# PAGE1.net
KiCad netlist of a schematic drawn in EAGLE
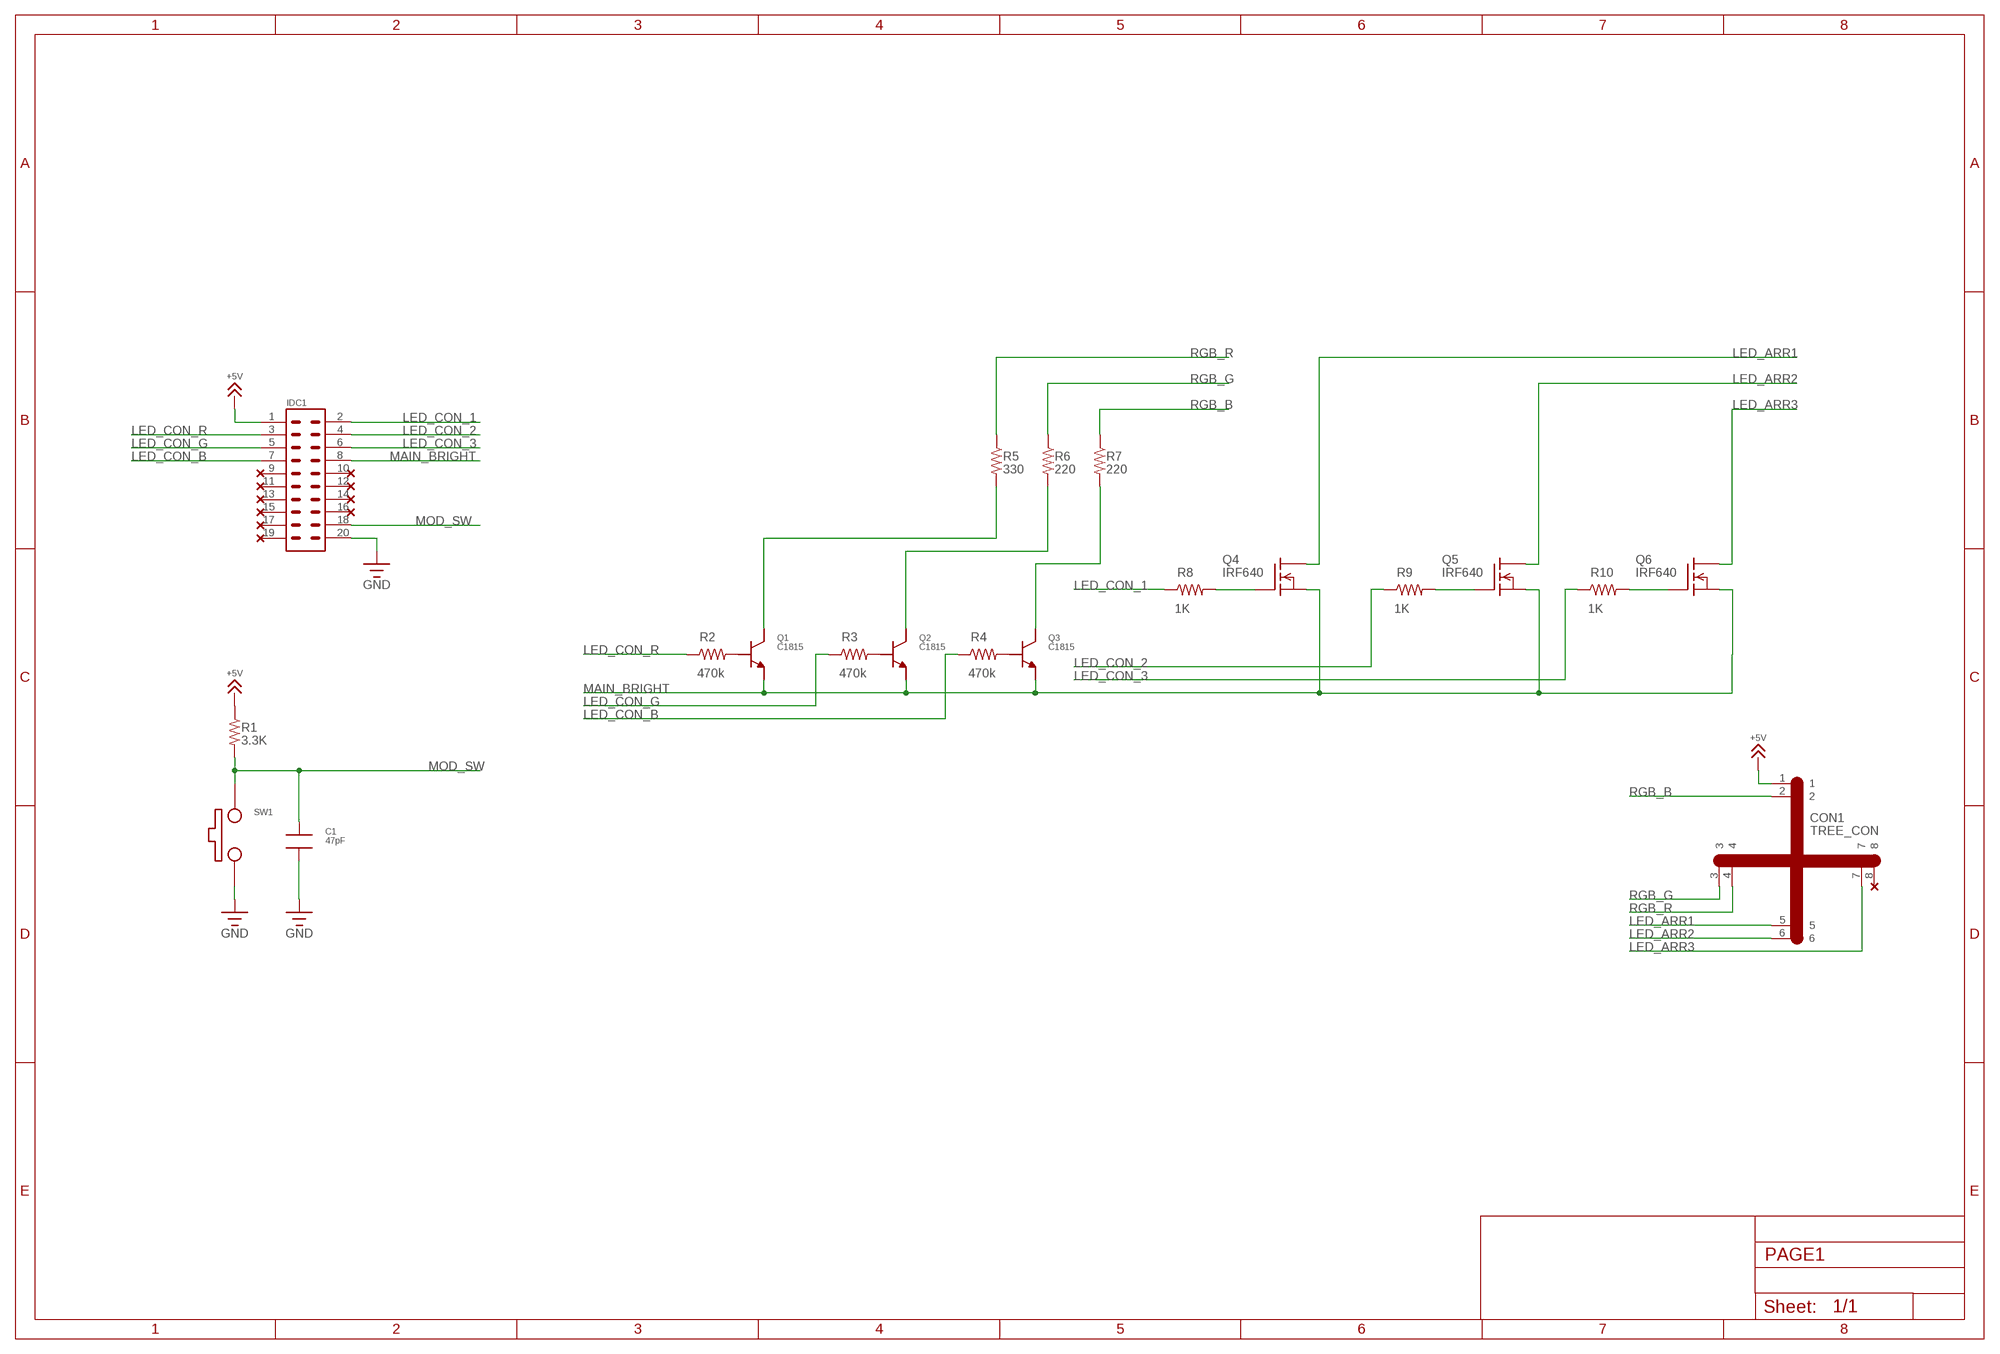
[diagram p0: schematic, sheet 1]

(export (version "E")
  (design (tool "Eeschema 10.0.6"))
  (components
    (comp (ref "C1")
      (value "47pF")
      (footprint "eagle-import:SMD2012")
      (libsource (lib "eagle-import") (part "CAP_NP_SMD2012"))
    )
    (comp (ref "CON1")
      (value "TREE_CON")
      (footprint "eagle-import:TREE_CON")
      (libsource (lib "eagle-import") (part "TREE_CON"))
    )
    (comp (ref "IDC1")
      (value "IDC20_BEN")
      (footprint "eagle-import:IDC20_BENDING")
      (libsource (lib "eagle-import") (part "IDC20_BEN"))
    )
    (comp (ref "Q1")
      (value "C1815")
      (footprint "eagle-import:TO92")
      (libsource (lib "eagle-import") (part "NPN"))
    )
    (comp (ref "Q2")
      (value "C1815")
      (footprint "eagle-import:TO92")
      (libsource (lib "eagle-import") (part "NPN"))
    )
    (comp (ref "Q3")
      (value "C1815")
      (footprint "eagle-import:TO92")
      (libsource (lib "eagle-import") (part "NPN"))
    )
    (comp (ref "Q4")
      (value "IRF640")
      (footprint "eagle-import:TO220")
      (libsource (lib "eagle-import") (part "IRF620"))
    )
    (comp (ref "Q5")
      (value "IRF640")
      (footprint "eagle-import:TO220")
      (libsource (lib "eagle-import") (part "IRF620"))
    )
    (comp (ref "Q6")
      (value "IRF640")
      (footprint "eagle-import:TO220")
      (libsource (lib "eagle-import") (part "IRF620"))
    )
    (comp (ref "R1")
      (value "3.3K")
      (footprint "eagle-import:SMD2012")
      (libsource (lib "eagle-import") (part "RES_2012"))
    )
    (comp (ref "R2")
      (value "470k")
      (footprint "eagle-import:SMD2012")
      (libsource (lib "eagle-import") (part "RES_2012"))
    )
    (comp (ref "R3")
      (value "470k")
      (footprint "eagle-import:SMD2012")
      (libsource (lib "eagle-import") (part "RES_2012"))
    )
    (comp (ref "R4")
      (value "470k")
      (footprint "eagle-import:SMD2012")
      (libsource (lib "eagle-import") (part "RES_2012"))
    )
    (comp (ref "R5")
      (value "330")
      (footprint "eagle-import:SMD2012")
      (libsource (lib "eagle-import") (part "RES_2012"))
    )
    (comp (ref "R6")
      (value "220")
      (footprint "eagle-import:SMD2012")
      (libsource (lib "eagle-import") (part "RES_2012"))
    )
    (comp (ref "R7")
      (value "220")
      (footprint "eagle-import:SMD2012")
      (libsource (lib "eagle-import") (part "RES_2012"))
    )
    (comp (ref "R8")
      (value "1K")
      (footprint "eagle-import:SMD2012")
      (libsource (lib "eagle-import") (part "RES_2012"))
    )
    (comp (ref "R9")
      (value "1K")
      (footprint "eagle-import:SMD2012")
      (libsource (lib "eagle-import") (part "RES_2012"))
    )
    (comp (ref "R10")
      (value "1K")
      (footprint "eagle-import:SMD2012")
      (libsource (lib "eagle-import") (part "RES_2012"))
    )
    (comp (ref "SW1")
      (value "PUSH_SW")
      (footprint "eagle-import:PUSH_SW")
      (libsource (lib "eagle-import") (part "PUSH_SW"))
    )
  )
  (nets
    (net (code "1") (name "+5V") (class "Default")
      (node (ref "CON1") (pin "1") (pinfunction "1_1") (pintype "passive"))
      (node (ref "IDC1") (pin "1") (pinfunction "1_1") (pintype "passive"))
      (node (ref "R1") (pin "1") (pinfunction "1_1") (pintype "passive"))
    )
    (net (code "2") (name "/LED_ARR1") (class "Default")
      (node (ref "CON1") (pin "5") (pinfunction "5_5") (pintype "passive"))
      (node (ref "Q4") (pin "2") (pinfunction "D_2") (pintype "passive"))
    )
    (net (code "3") (name "/LED_ARR2") (class "Default")
      (node (ref "CON1") (pin "6") (pinfunction "6_6") (pintype "passive"))
      (node (ref "Q5") (pin "2") (pinfunction "D_2") (pintype "passive"))
    )
    (net (code "4") (name "/LED_ARR3") (class "Default")
      (node (ref "CON1") (pin "7") (pinfunction "7_7") (pintype "passive"))
      (node (ref "Q6") (pin "2") (pinfunction "D_2") (pintype "passive"))
    )
    (net (code "5") (name "/LED_CON_1") (class "Default")
      (node (ref "IDC1") (pin "2") (pinfunction "2_2") (pintype "passive"))
      (node (ref "R8") (pin "1") (pinfunction "1_1") (pintype "passive"))
    )
    (net (code "6") (name "/LED_CON_2") (class "Default")
      (node (ref "IDC1") (pin "4") (pinfunction "4_4") (pintype "passive"))
      (node (ref "R9") (pin "1") (pinfunction "1_1") (pintype "passive"))
    )
    (net (code "7") (name "/LED_CON_3") (class "Default")
      (node (ref "IDC1") (pin "6") (pinfunction "6_6") (pintype "passive"))
      (node (ref "R10") (pin "1") (pinfunction "1_1") (pintype "passive"))
    )
    (net (code "8") (name "/LED_CON_B") (class "Default")
      (node (ref "IDC1") (pin "7") (pinfunction "7_7") (pintype "passive"))
      (node (ref "R4") (pin "1") (pinfunction "1_1") (pintype "passive"))
    )
    (net (code "9") (name "/LED_CON_G") (class "Default")
      (node (ref "IDC1") (pin "5") (pinfunction "5_5") (pintype "passive"))
      (node (ref "R3") (pin "1") (pinfunction "1_1") (pintype "passive"))
    )
    (net (code "10") (name "/LED_CON_R") (class "Default")
      (node (ref "IDC1") (pin "3") (pinfunction "3_3") (pintype "passive"))
      (node (ref "R2") (pin "1") (pinfunction "1_1") (pintype "passive"))
    )
    (net (code "11") (name "/MAIN_BRIGHT") (class "Default")
      (node (ref "IDC1") (pin "8") (pinfunction "8_8") (pintype "passive"))
      (node (ref "Q1") (pin "1") (pinfunction "E_1") (pintype "passive"))
      (node (ref "Q2") (pin "1") (pinfunction "E_1") (pintype "passive"))
      (node (ref "Q3") (pin "1") (pinfunction "E_1") (pintype "passive"))
      (node (ref "Q4") (pin "3") (pinfunction "S_3") (pintype "passive"))
      (node (ref "Q5") (pin "3") (pinfunction "S_3") (pintype "passive"))
      (node (ref "Q6") (pin "3") (pinfunction "S_3") (pintype "passive"))
    )
    (net (code "12") (name "/MOD_SW") (class "Default")
      (node (ref "C1") (pin "1") (pinfunction "1_1") (pintype "passive"))
      (node (ref "IDC1") (pin "18") (pinfunction "18_18") (pintype "passive"))
      (node (ref "R1") (pin "2") (pinfunction "2_2") (pintype "passive"))
      (node (ref "SW1") (pin "P$2") (pinfunction "P$2_P$2") (pintype "passive"))
    )
    (net (code "13") (name "/RGB_B") (class "Default")
      (node (ref "CON1") (pin "2") (pinfunction "2_2") (pintype "passive"))
      (node (ref "R7") (pin "1") (pinfunction "1_1") (pintype "passive"))
    )
    (net (code "14") (name "/RGB_G") (class "Default")
      (node (ref "CON1") (pin "3") (pinfunction "3_3") (pintype "passive"))
      (node (ref "R6") (pin "1") (pinfunction "1_1") (pintype "passive"))
    )
    (net (code "15") (name "/RGB_R") (class "Default")
      (node (ref "CON1") (pin "4") (pinfunction "4_4") (pintype "passive"))
      (node (ref "R5") (pin "1") (pinfunction "1_1") (pintype "passive"))
    )
    (net (code "16") (name "GND") (class "Default")
      (node (ref "C1") (pin "2") (pinfunction "2_2") (pintype "passive"))
      (node (ref "IDC1") (pin "20") (pinfunction "20_20") (pintype "passive"))
      (node (ref "SW1") (pin "P$1") (pinfunction "P$1_P$1") (pintype "passive"))
    )
    (net (code "17") (name "Net-(Q1-B)") (class "Default")
      (node (ref "Q1") (pin "3") (pinfunction "B_3") (pintype "passive"))
      (node (ref "R2") (pin "2") (pinfunction "2_2") (pintype "passive"))
    )
    (net (code "18") (name "Net-(Q1-C)") (class "Default")
      (node (ref "Q1") (pin "2") (pinfunction "C_2") (pintype "passive"))
      (node (ref "R5") (pin "2") (pinfunction "2_2") (pintype "passive"))
    )
    (net (code "19") (name "Net-(Q2-B)") (class "Default")
      (node (ref "Q2") (pin "3") (pinfunction "B_3") (pintype "passive"))
      (node (ref "R3") (pin "2") (pinfunction "2_2") (pintype "passive"))
    )
    (net (code "20") (name "Net-(Q2-C)") (class "Default")
      (node (ref "Q2") (pin "2") (pinfunction "C_2") (pintype "passive"))
      (node (ref "R6") (pin "2") (pinfunction "2_2") (pintype "passive"))
    )
    (net (code "21") (name "Net-(Q3-B)") (class "Default")
      (node (ref "Q3") (pin "3") (pinfunction "B_3") (pintype "passive"))
      (node (ref "R4") (pin "2") (pinfunction "2_2") (pintype "passive"))
    )
    (net (code "22") (name "Net-(Q3-C)") (class "Default")
      (node (ref "Q3") (pin "2") (pinfunction "C_2") (pintype "passive"))
      (node (ref "R7") (pin "2") (pinfunction "2_2") (pintype "passive"))
    )
    (net (code "23") (name "Net-(Q4-G)") (class "Default")
      (node (ref "Q4") (pin "1") (pinfunction "G_1") (pintype "passive"))
      (node (ref "R8") (pin "2") (pinfunction "2_2") (pintype "passive"))
    )
    (net (code "24") (name "Net-(Q5-G)") (class "Default")
      (node (ref "Q5") (pin "1") (pinfunction "G_1") (pintype "passive"))
      (node (ref "R9") (pin "2") (pinfunction "2_2") (pintype "passive"))
    )
    (net (code "25") (name "Net-(Q6-G)") (class "Default")
      (node (ref "Q6") (pin "1") (pinfunction "G_1") (pintype "passive"))
      (node (ref "R10") (pin "2") (pinfunction "2_2") (pintype "passive"))
    )
    (net (code "26") (name "unconnected-(CON1-Pad8)") (class "Default")
      (node (ref "CON1") (pin "8") (pinfunction "8_8") (pintype "passive"))
    )
    (net (code "27") (name "unconnected-(IDC1-Pad9)") (class "Default")
      (node (ref "IDC1") (pin "9") (pinfunction "9_9") (pintype "passive"))
    )
    (net (code "28") (name "unconnected-(IDC1-Pad10)") (class "Default")
      (node (ref "IDC1") (pin "10") (pinfunction "10_10") (pintype "passive"))
    )
    (net (code "29") (name "unconnected-(IDC1-Pad11)") (class "Default")
      (node (ref "IDC1") (pin "11") (pinfunction "11_11") (pintype "passive"))
    )
    (net (code "30") (name "unconnected-(IDC1-Pad12)") (class "Default")
      (node (ref "IDC1") (pin "12") (pinfunction "12_12") (pintype "passive"))
    )
    (net (code "31") (name "unconnected-(IDC1-Pad13)") (class "Default")
      (node (ref "IDC1") (pin "13") (pinfunction "13_13") (pintype "passive"))
    )
    (net (code "32") (name "unconnected-(IDC1-Pad14)") (class "Default")
      (node (ref "IDC1") (pin "14") (pinfunction "14_14") (pintype "passive"))
    )
    (net (code "33") (name "unconnected-(IDC1-Pad15)") (class "Default")
      (node (ref "IDC1") (pin "15") (pinfunction "15_15") (pintype "passive"))
    )
    (net (code "34") (name "unconnected-(IDC1-Pad16)") (class "Default")
      (node (ref "IDC1") (pin "16") (pinfunction "16_16") (pintype "passive"))
    )
    (net (code "35") (name "unconnected-(IDC1-Pad17)") (class "Default")
      (node (ref "IDC1") (pin "17") (pinfunction "17_17") (pintype "passive"))
    )
    (net (code "36") (name "unconnected-(IDC1-Pad19)") (class "Default")
      (node (ref "IDC1") (pin "19") (pinfunction "19_19") (pintype "passive"))
    )
  )
)
